# Power.net
KiCad netlist of a schematic drawn in Altium Designer
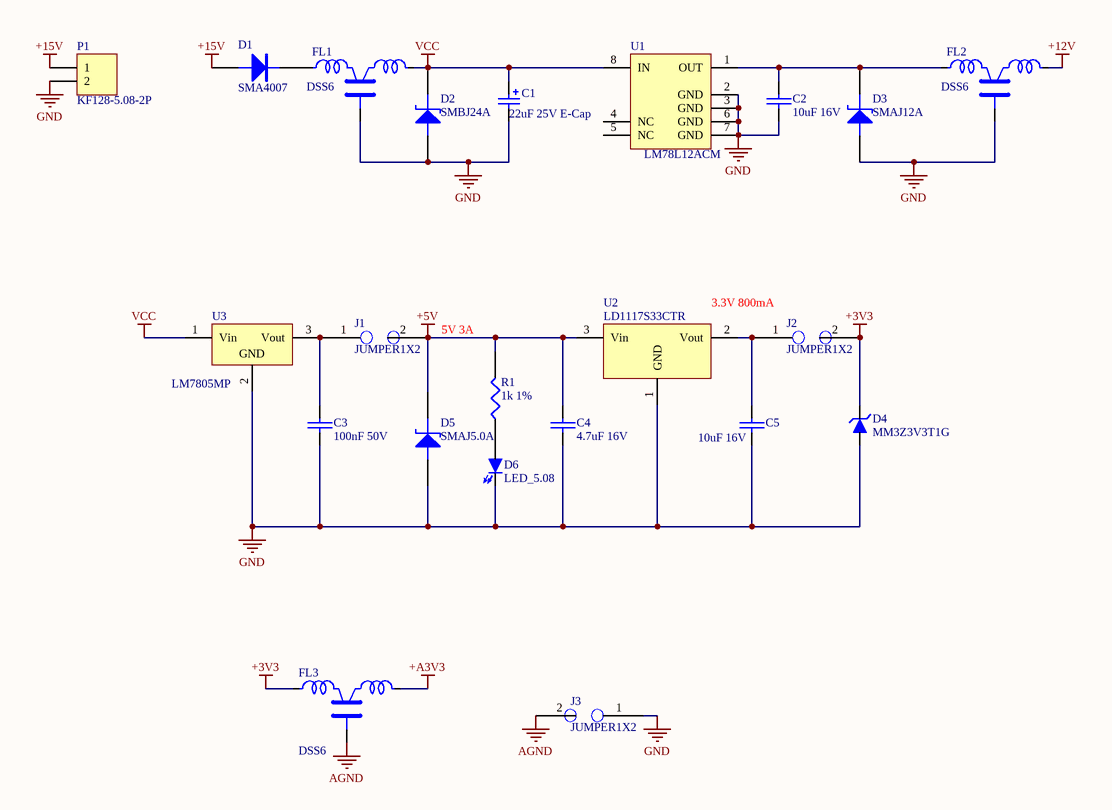
[diagram p0: Power.SchDoc]

(export (version "E")
  (design (tool "Eeschema 10.0.6"))
  (components
    (comp (ref "C1")
      (value "22uF 25V E-Cap")
      (footprint "SemTech E-Cap:SMT E-Cap 5x5.4")
      (description "Polarized Capacitor (Radial)")
      (fields (field (name "PUBLISHER") "Altium Limited"))
      (libsource (lib "Miscellaneous Devices") (part "Cap Pol1"))
    )
    (comp (ref "C2")
      (value "10uF 16V")
      (footprint "Chip_Capacitor_N:CAPC3216N")
      (libsource (lib "*") (part "CAP"))
    )
    (comp (ref "C3")
      (value "100nF 50V")
      (footprint "Chip_Capacitor_N:CAPC2012N")
      (libsource (lib "*") (part "CAP"))
    )
    (comp (ref "C4")
      (value "4.7uF 16V")
      (footprint "Chip_Capacitor_N:CAPC2012N")
      (libsource (lib "*") (part "CAP"))
    )
    (comp (ref "C5")
      (value "10uF 16V")
      (footprint "Chip_Capacitor_N:CAPC3216N")
      (libsource (lib "*") (part "CAP"))
    )
    (comp (ref "D1")
      (value "SMA4007")
      (footprint "Small Outline Diode - 2 C-Bend Leads:DSO-C2/G1.6")
      (description "Diode")
      (libsource (lib "*") (part "DIODE"))
    )
    (comp (ref "D2")
      (value "SMBJ24A")
      (footprint "Small Outline Diode - 2 C-Bend Leads:DSO-C2/X2.3")
      (description "Zener Diode")
      (libsource (lib "*") (part "ZENER2"))
    )
    (comp (ref "D3")
      (value "SMAJ12A")
      (footprint "Small Outline Diode - 2 C-Bend Leads:DSO-C2/G1.6")
      (description "Zener Diode")
      (fields (field (name "MANUFACTURER") "Littlefuse"))
      (libsource (lib "*") (part "ZENER2"))
    )
    (comp (ref "D4")
      (value "MM3Z3V3T1G")
      (footprint "Small Outline Diode - 2 Gullwing Leads:SOD-323")
      (description "Zener diode")
      (fields (field (name "MANUFACTURER") "ON"))
      (libsource (lib "UserSchlib") (part "Zener Diode"))
    )
    (comp (ref "D5")
      (value "SMAJ5.0A")
      (footprint "Small Outline Diode - 2 C-Bend Leads:DSO-C2/G1.6")
      (description "Zener Diode")
      (fields (field (name "MANUFACTURER") "Vishay"))
      (libsource (lib "*") (part "ZENER2"))
    )
    (comp (ref "D6")
      (value "LED_5.08")
      (footprint "UserPcbLib:LED5.08/2.54-2")
      (description "Through hole LED dia.5.08")
      (libsource (lib "UserSchlib") (part "LED_5.08"))
    )
    (comp (ref "FL1")
      (value "DSS6")
      (footprint "UserPcbLib:DSS6")
      (description "Murata EMI suppression filter")
      (fields (field (name "MANUFACTURER") "Murata"))
      (libsource (lib "UserSchlib") (part "DSS6"))
    )
    (comp (ref "FL2")
      (value "DSS6")
      (footprint "UserPcbLib:DSS6")
      (description "Murata EMI suppression filter")
      (fields (field (name "MANUFACTURER") "Murata"))
      (libsource (lib "UserSchlib") (part "DSS6"))
    )
    (comp (ref "FL3")
      (value "DSS6")
      (footprint "UserPcbLib:DSS6")
      (description "Murata EMI suppression filter")
      (fields (field (name "MANUFACTURER") "Murata"))
      (libsource (lib "UserSchlib") (part "DSS6"))
    )
    (comp (ref "J1")
      (value "JUMPER1X2")
      (footprint "UserPcbLib:JP-SOLDER-H1X2-3X2")
      (libsource (lib "*") (part "JUMPER1X2"))
    )
    (comp (ref "J2")
      (value "JUMPER1X2")
      (footprint "UserPcbLib:JP-SOLDER-H1X2-3X2")
      (libsource (lib "*") (part "JUMPER1X2"))
    )
    (comp (ref "J3")
      (value "JUMPER1X2")
      (footprint "UserPcbLib:JP-SOLDER-H1X2-3X2")
      (libsource (lib "Peter") (part "JUMPER1X2"))
    )
    (comp (ref "P1")
      (value "KF128-5.08-2P")
      (footprint "UserPcbLib:KF128-5.08-2P")
      (description "Power supply connector")
      (fields (field (name "PUBLISHER") "Altium Limited"))
      (libsource (lib "Miscellaneous Connectors") (part "Header 2"))
    )
    (comp (ref "R1")
      (value "1k 1%")
      (footprint "Chip_Resistor_N:RESC2012N")
      (libsource (lib "*") (part "RES1"))
    )
    (comp (ref "U1")
      (value "LM78L12ACM")
      (footprint "ST-Microelectronics Footprints:SO8_M")
      (description "3-Terminal Positive Regulators")
      (fields
        (field (name "PARTNUMBER") "LM78L05ACM")
        (field (name "MANUFACTURER") "National Semiconductor")
        (field (name "PUBLISHER") "Altium Limited")
      )
      (libsource (lib "NSC LDO") (part "LM78L05ACM"))
    )
    (comp (ref "U2")
      (value "LD1117S33CTR")
      (footprint "SOT223_M:SOT223-4M")
      (description "ST Low drop voltage regulator")
      (fields (field (name "MANUFACTURER") "ST"))
      (libsource (lib "*") (part "VOLTREG"))
    )
    (comp (ref "U3")
      (value "LM7805MP")
      (footprint "SOT223_M:SOT223-4M")
      (description "Voltage Regulator")
      (fields (field (name "PUBLISHER") "Altium Limited"))
      (libsource (lib "Miscellaneous Devices") (part "Volt Reg"))
    )
  )
  (nets
    (net (code "1") (name "+3V3") (class "Default")
      (node (ref "D4") (pin "1") (pinfunction "K_1") (pintype "passive"))
      (node (ref "FL3") (pin "1") (pinfunction "1_1") (pintype "passive"))
      (node (ref "J2") (pin "2") (pinfunction "1_2") (pintype "passive"))
    )
    (net (code "2") (name "+5V") (class "Default")
      (node (ref "C4") (pin "1") (pintype "passive"))
      (node (ref "D5") (pin "2") (pinfunction "K_2") (pintype "passive"))
      (node (ref "J1") (pin "2") (pinfunction "1_2") (pintype "passive"))
      (node (ref "R1") (pin "2") (pinfunction "2_2") (pintype "passive"))
      (node (ref "U2") (pin "3") (pinfunction "Vin_3") (pintype "passive"))
    )
    (net (code "3") (name "+12V") (class "Default")
      (node (ref "FL2") (pin "3") (pinfunction "3_3") (pintype "passive"))
    )
    (net (code "4") (name "+15V") (class "Default")
      (node (ref "D1") (pin "1") (pinfunction "A_1") (pintype "passive"))
      (node (ref "P1") (pin "1") (pinfunction "1_1") (pintype "passive"))
    )
    (net (code "5") (name "+A3V3") (class "Default")
      (node (ref "FL3") (pin "3") (pinfunction "3_3") (pintype "passive"))
    )
    (net (code "6") (name "AGND") (class "Default")
      (node (ref "FL3") (pin "2") (pinfunction "2_2") (pintype "passive"))
      (node (ref "J3") (pin "2") (pinfunction "1_2") (pintype "passive"))
    )
    (net (code "7") (name "GND") (class "Default")
      (node (ref "C1") (pin "2") (pinfunction "2_2") (pintype "passive"))
      (node (ref "C2") (pin "2") (pintype "passive"))
      (node (ref "C3") (pin "1") (pintype "passive"))
      (node (ref "C4") (pin "2") (pintype "passive"))
      (node (ref "C5") (pin "2") (pintype "passive"))
      (node (ref "D2") (pin "1") (pinfunction "A_1") (pintype "passive"))
      (node (ref "D3") (pin "1") (pinfunction "A_1") (pintype "passive"))
      (node (ref "D4") (pin "2") (pinfunction "A_2") (pintype "passive"))
      (node (ref "D5") (pin "1") (pinfunction "A_1") (pintype "passive"))
      (node (ref "D6") (pin "2") (pinfunction "K_2") (pintype "passive"))
      (node (ref "FL1") (pin "2") (pinfunction "2_2") (pintype "passive"))
      (node (ref "FL2") (pin "2") (pinfunction "2_2") (pintype "passive"))
      (node (ref "J3") (pin "1") (pinfunction "0_1") (pintype "passive"))
      (node (ref "P1") (pin "2") (pinfunction "2_2") (pintype "passive"))
      (node (ref "U1") (pin "2") (pinfunction "GND_2") (pintype "power_in"))
      (node (ref "U1") (pin "3") (pinfunction "GND_3") (pintype "power_in"))
      (node (ref "U1") (pin "6") (pinfunction "GND_6") (pintype "power_in"))
      (node (ref "U1") (pin "7") (pinfunction "GND_7") (pintype "power_in"))
      (node (ref "U2") (pin "1") (pinfunction "GND_1") (pintype "passive"))
      (node (ref "U3") (pin "2") (pinfunction "GND_2") (pintype "passive"))
    )
    (net (code "8") (name "Net-(D1-K)") (class "Default")
      (node (ref "D1") (pin "2") (pinfunction "K_2") (pintype "passive"))
      (node (ref "FL1") (pin "1") (pinfunction "1_1") (pintype "passive"))
    )
    (net (code "9") (name "Net-(D3-K)") (class "Default")
      (node (ref "C2") (pin "1") (pintype "passive"))
      (node (ref "D3") (pin "2") (pinfunction "K_2") (pintype "passive"))
      (node (ref "FL2") (pin "1") (pinfunction "1_1") (pintype "passive"))
      (node (ref "U1") (pin "1") (pinfunction "OUT_1") (pintype "power_in"))
    )
    (net (code "10") (name "Net-(D6-A)") (class "Default")
      (node (ref "D6") (pin "1") (pinfunction "A_1") (pintype "passive"))
      (node (ref "R1") (pin "1") (pinfunction "1_1") (pintype "passive"))
    )
    (net (code "11") (name "Net-(J1-0)") (class "Default")
      (node (ref "C3") (pin "2") (pintype "passive"))
      (node (ref "J1") (pin "1") (pinfunction "0_1") (pintype "passive"))
      (node (ref "U3") (pin "3") (pinfunction "Vout_3") (pintype "passive"))
    )
    (net (code "12") (name "Net-(J2-0)") (class "Default")
      (node (ref "C5") (pin "1") (pintype "passive"))
      (node (ref "J2") (pin "1") (pinfunction "0_1") (pintype "passive"))
      (node (ref "U2") (pin "2") (pinfunction "Vout_2") (pintype "passive"))
    )
    (net (code "13") (name "VCC") (class "Default")
      (node (ref "C1") (pin "1") (pinfunction "1_1") (pintype "passive"))
      (node (ref "D2") (pin "2") (pinfunction "K_2") (pintype "passive"))
      (node (ref "FL1") (pin "3") (pinfunction "3_3") (pintype "passive"))
      (node (ref "U1") (pin "8") (pinfunction "IN_8") (pintype "power_in"))
      (node (ref "U3") (pin "1") (pinfunction "Vin_1") (pintype "passive"))
    )
    (net (code "14") (name "unconnected-(U1-NC-Pad4)") (class "Default")
      (node (ref "U1") (pin "4") (pinfunction "NC_4") (pintype "passive"))
    )
    (net (code "15") (name "unconnected-(U1-NC-Pad5)") (class "Default")
      (node (ref "U1") (pin "5") (pinfunction "NC_5") (pintype "passive"))
    )
  )
)
